# Blinklicht_V1-0.net
KiCad netlist of a schematic drawn in EAGLE
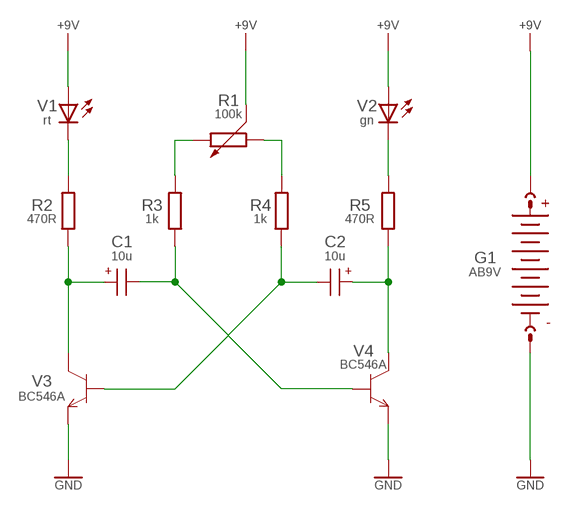
[diagram p0: schematic, sheet 1]

(export (version "E")
  (design (tool "Eeschema 10.0.6"))
  (components
    (comp (ref "C1")
      (value "10u")
      (footprint "eagle-import:E2-5")
      (libsource (lib "eagle-import") (part "CPOL-EUE2-5"))
    )
    (comp (ref "C2")
      (value "10u")
      (footprint "eagle-import:E2-5")
      (libsource (lib "eagle-import") (part "CPOL-EUE2-5"))
    )
    (comp (ref "G1")
      (value "AB9V")
      (footprint "eagle-import:AB9V")
      (libsource (lib "eagle-import") (part "AB9V"))
    )
    (comp (ref "R1")
      (value "100k")
      (footprint "eagle-import:PT-10")
      (libsource (lib "eagle-import") (part "POTENTIOMETER_PT-10"))
    )
    (comp (ref "R2")
      (value "470R")
      (footprint "eagle-import:0207_10")
      (libsource (lib "eagle-import") (part "R-EU_0207/10"))
    )
    (comp (ref "R3")
      (value "1k")
      (footprint "eagle-import:0207_10")
      (libsource (lib "eagle-import") (part "R-EU_0207/10"))
    )
    (comp (ref "R4")
      (value "1k")
      (footprint "eagle-import:0207_10")
      (libsource (lib "eagle-import") (part "R-EU_0207/10"))
    )
    (comp (ref "R5")
      (value "470R")
      (footprint "eagle-import:0207_10")
      (libsource (lib "eagle-import") (part "R-EU_0207/10"))
    )
    (comp (ref "V1")
      (value "rt")
      (footprint "eagle-import:LED3MM")
      (libsource (lib "eagle-import") (part "LED3MM"))
    )
    (comp (ref "V2")
      (value "gn")
      (footprint "eagle-import:LED3MM")
      (libsource (lib "eagle-import") (part "LED3MM"))
    )
    (comp (ref "V3")
      (value "BC546A")
      (footprint "eagle-import:TO92-EBC")
      (libsource (lib "eagle-import") (part "BC546A"))
    )
    (comp (ref "V4")
      (value "BC546A")
      (footprint "eagle-import:TO92-EBC")
      (libsource (lib "eagle-import") (part "BC546A"))
    )
  )
  (nets
    (net (code "1") (name "+9V") (class "Default")
      (node (ref "G1") (pin "+") (pinfunction "+_+") (pintype "passive"))
      (node (ref "R1") (pin "3") (pinfunction "3_3") (pintype "passive"))
      (node (ref "V1") (pin "A") (pinfunction "A_A") (pintype "passive"))
      (node (ref "V2") (pin "A") (pinfunction "A_A") (pintype "passive"))
    )
    (net (code "2") (name "GND") (class "Default")
      (node (ref "G1") (pin "-") (pinfunction "-_-") (pintype "passive"))
      (node (ref "V3") (pin "E") (pinfunction "E_E") (pintype "passive"))
      (node (ref "V4") (pin "E") (pinfunction "E_E") (pintype "passive"))
    )
    (net (code "3") (name "Net-(C1-Pad+)") (class "Default")
      (node (ref "C1") (pin "+") (pinfunction "+_+") (pintype "passive"))
      (node (ref "R2") (pin "1") (pinfunction "1_1") (pintype "passive"))
      (node (ref "V3") (pin "C") (pinfunction "C_C") (pintype "passive"))
    )
    (net (code "4") (name "Net-(C1-Pad-)") (class "Default")
      (node (ref "C1") (pin "-") (pinfunction "-_-") (pintype "passive"))
      (node (ref "R3") (pin "1") (pinfunction "1_1") (pintype "passive"))
      (node (ref "V4") (pin "B") (pinfunction "B_B") (pintype "passive"))
    )
    (net (code "5") (name "Net-(C2-Pad+)") (class "Default")
      (node (ref "C2") (pin "+") (pinfunction "+_+") (pintype "passive"))
      (node (ref "R5") (pin "1") (pinfunction "1_1") (pintype "passive"))
      (node (ref "V4") (pin "C") (pinfunction "C_C") (pintype "passive"))
    )
    (net (code "6") (name "Net-(C2-Pad-)") (class "Default")
      (node (ref "C2") (pin "-") (pinfunction "-_-") (pintype "passive"))
      (node (ref "R4") (pin "1") (pinfunction "1_1") (pintype "passive"))
      (node (ref "V3") (pin "B") (pinfunction "B_B") (pintype "passive"))
    )
    (net (code "7") (name "Net-(R1-Pad1)") (class "Default")
      (node (ref "R1") (pin "1") (pinfunction "1_1") (pintype "passive"))
      (node (ref "R4") (pin "2") (pinfunction "2_2") (pintype "passive"))
    )
    (net (code "8") (name "Net-(R1-Pad2)") (class "Default")
      (node (ref "R1") (pin "2") (pinfunction "2_2") (pintype "passive"))
      (node (ref "R3") (pin "2") (pinfunction "2_2") (pintype "passive"))
    )
    (net (code "9") (name "Net-(V1-C)") (class "Default")
      (node (ref "R2") (pin "2") (pinfunction "2_2") (pintype "passive"))
      (node (ref "V1") (pin "K") (pinfunction "C_K") (pintype "passive"))
    )
    (net (code "10") (name "Net-(V2-C)") (class "Default")
      (node (ref "R5") (pin "2") (pinfunction "2_2") (pintype "passive"))
      (node (ref "V2") (pin "K") (pinfunction "C_K") (pintype "passive"))
    )
  )
)
